# LKS_EVB_MVPOWPRE_V5_0.net
KiCad netlist of a schematic drawn in Altium Designer
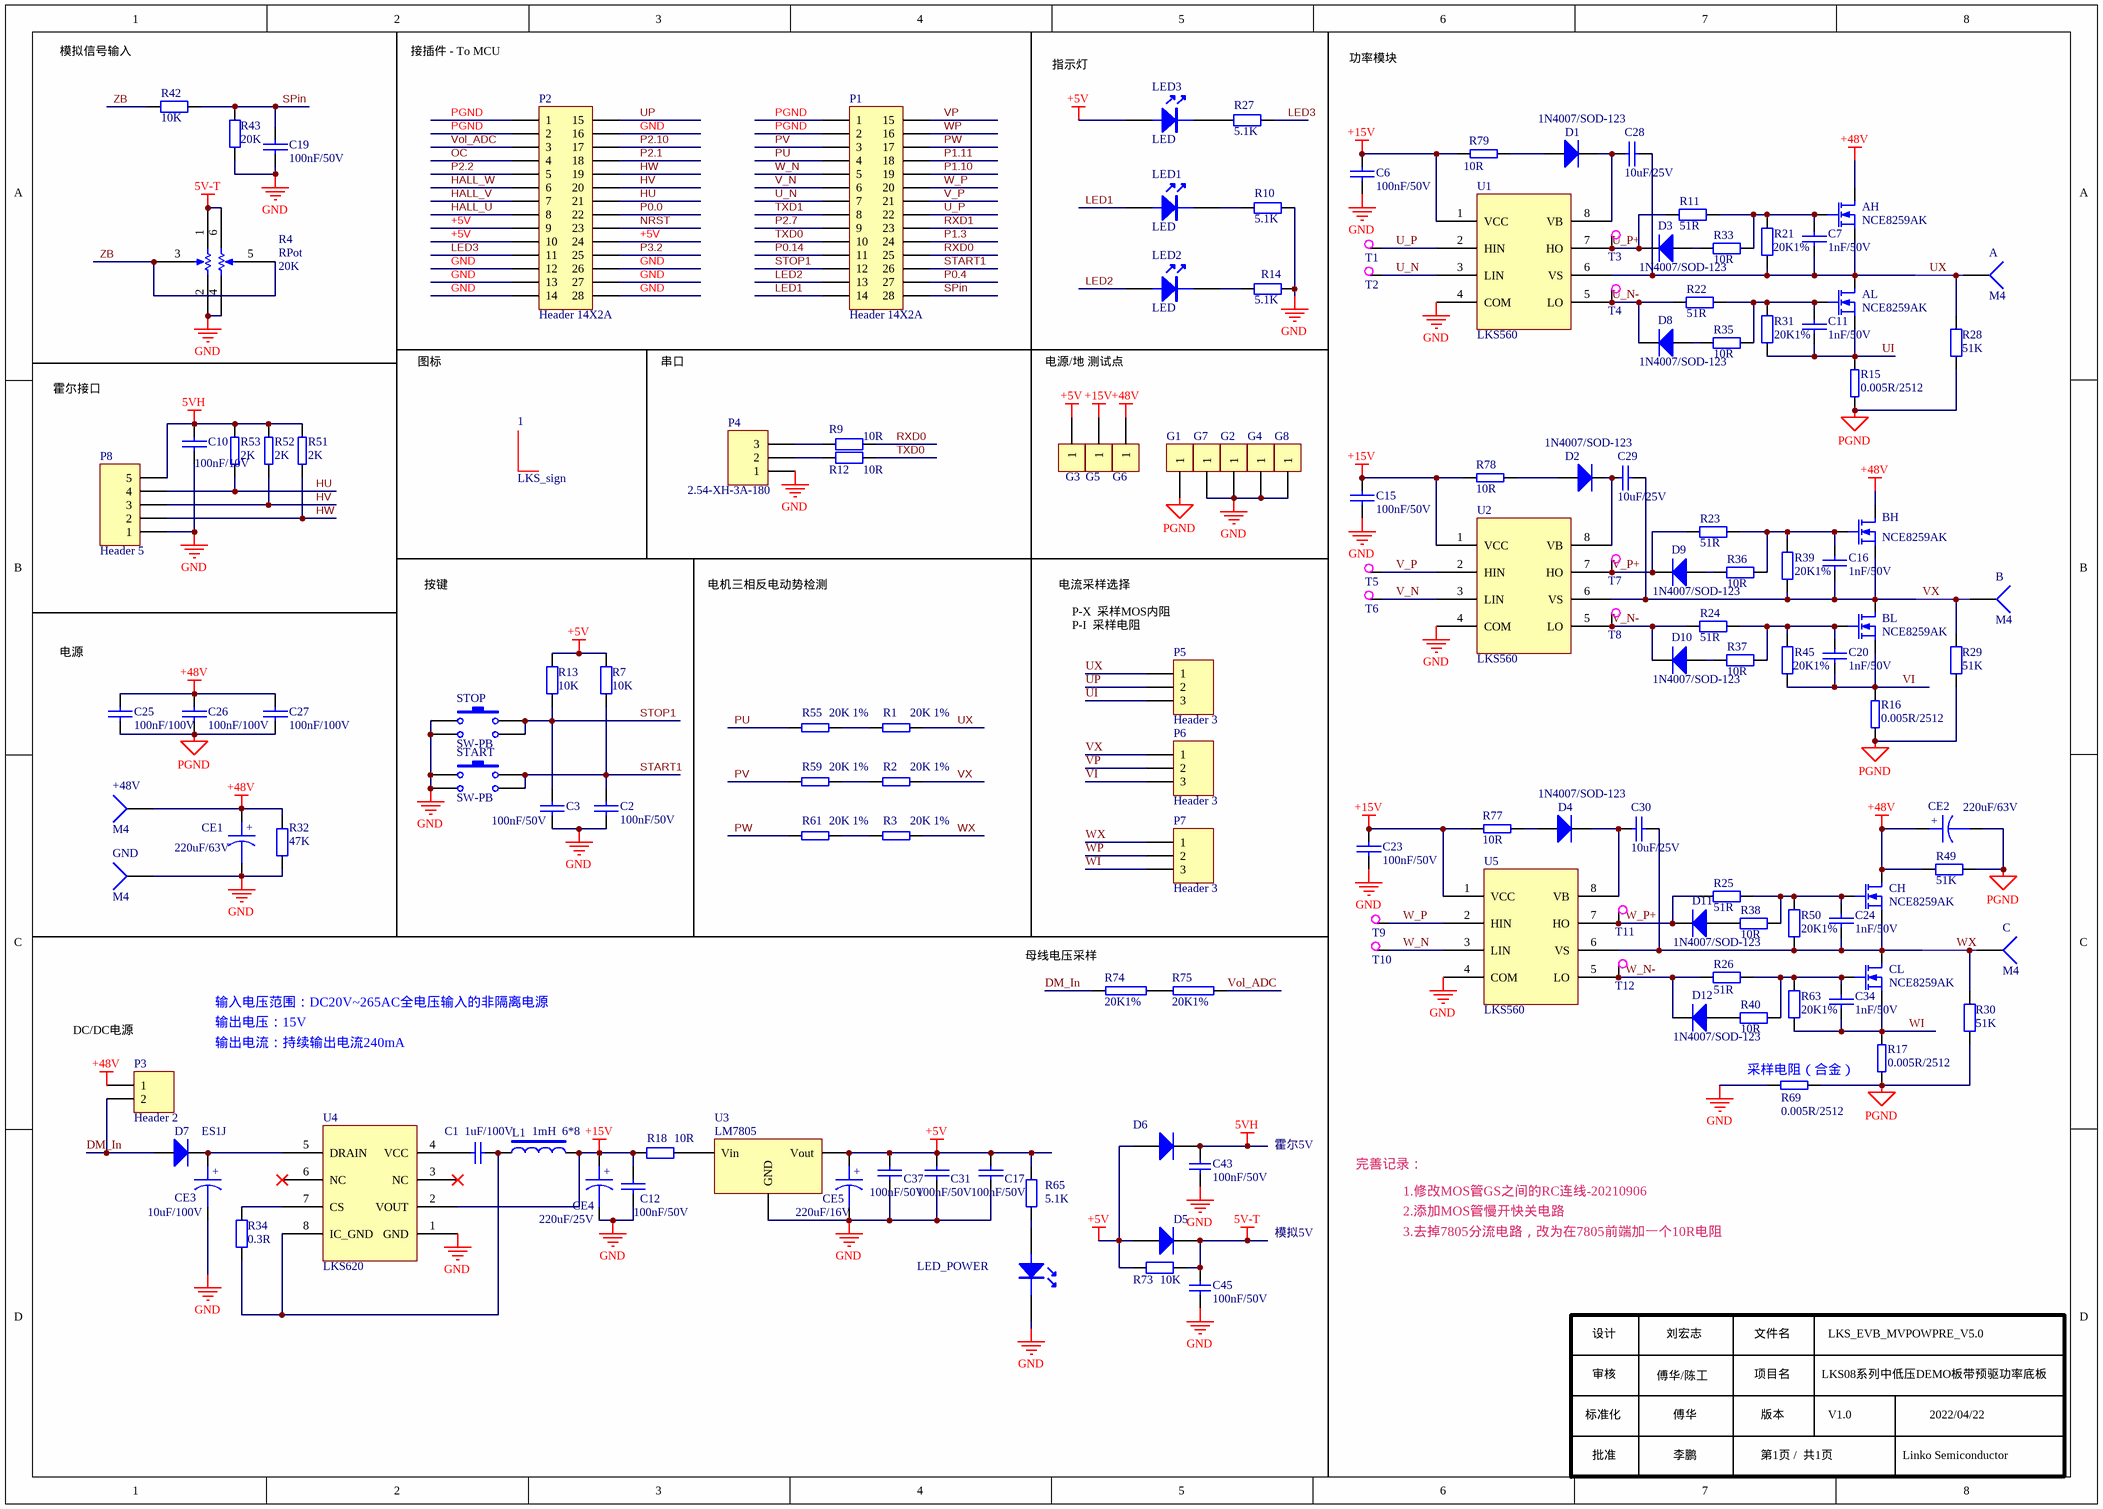
[diagram p0: LKS_EVB_MVPOWPRE_V5.0.SchDoc]

(export (version "E")
  (design (tool "Eeschema 10.0.6"))
  (components
    (comp (ref "+48V")
      (value "M4")
      (footprint "M4_CONECTOR")
      (description "Socket")
      (fields (field (name "PUBLISHER") "Altium Limited"))
      (libsource (lib "Miscellaneous Connectors") (part "Socket"))
    )
    (comp (ref "1")
      (value "LKS_sign")
      (footprint "LKS_LOGO2")
      (libsource (lib "linko sch library") (part "LKS_sign"))
    )
    (comp (ref "A")
      (value "M4")
      (footprint "M4_Conector")
      (description "Socket")
      (fields (field (name "PUBLISHER") "Altium Limited"))
      (libsource (lib "*") (part "Socket"))
    )
    (comp (ref "AH")
      (value "NCE8259AK")
      (footprint "TO-252")
      (libsource (lib "POWER-conponent") (part "MOS"))
    )
    (comp (ref "AL")
      (value "NCE8259AK")
      (footprint "TO-252")
      (libsource (lib "POWER-conponent") (part "MOS"))
    )
    (comp (ref "B")
      (value "M4")
      (footprint "M4_Conector")
      (description "Socket")
      (fields (field (name "PUBLISHER") "Altium Limited"))
      (libsource (lib "*") (part "Socket"))
    )
    (comp (ref "BH")
      (value "NCE8259AK")
      (footprint "TO-252")
      (libsource (lib "POWER-conponent") (part "MOS"))
    )
    (comp (ref "BL")
      (value "NCE8259AK")
      (footprint "TO-252")
      (libsource (lib "POWER-conponent") (part "MOS"))
    )
    (comp (ref "C")
      (value "M4")
      (footprint "M4_Conector")
      (description "Socket")
      (fields (field (name "PUBLISHER") "Altium Limited"))
      (libsource (lib "*") (part "Socket"))
    )
    (comp (ref "C1")
      (value "1uF/100V")
      (footprint "1206")
      (description "Capacitor")
      (fields (field (name "PUBLISHER") "Altium Limited"))
      (libsource (lib "Miscellaneous Devices") (part "Cap"))
    )
    (comp (ref "C2")
      (value "100nF/50V")
      (footprint "0603C")
      (description "Capacitor")
      (libsource (lib "GJ-BC-IC") (part "CAP"))
    )
    (comp (ref "C3")
      (value "100nF/50V")
      (footprint "0603C")
      (description "Capacitor")
      (libsource (lib "GJ-BC-IC") (part "CAP"))
    )
    (comp (ref "C6")
      (value "100nF/50V")
      (footprint "0603C")
      (description "Capacitor")
      (libsource (lib "*") (part "C"))
    )
    (comp (ref "C7")
      (value "1nF/50V")
      (footprint "0603C")
      (description "Capacitor")
      (libsource (lib "") (part "CAP_1"))
    )
    (comp (ref "C10")
      (value "100nF/10V")
      (footprint "0603C")
      (description "Capacitor")
      (libsource (lib "GJ-BC-IC") (part "CAP"))
    )
    (comp (ref "C11")
      (value "1nF/50V")
      (footprint "0603C")
      (description "Capacitor")
      (libsource (lib "") (part "CAP_1"))
    )
    (comp (ref "C12")
      (value "100nF/50V")
      (footprint "0603C")
      (description "Capacitor")
      (libsource (lib "*") (part "CAP"))
    )
    (comp (ref "C15")
      (value "100nF/50V")
      (footprint "0603C")
      (description "Capacitor")
      (libsource (lib "*") (part "C"))
    )
    (comp (ref "C16")
      (value "1nF/50V")
      (footprint "0603C")
      (description "Capacitor")
      (libsource (lib "") (part "CAP_1"))
    )
    (comp (ref "C17")
      (value "100nF/50V")
      (footprint "0603C")
      (description "Capacitor")
      (libsource (lib "*") (part "C"))
    )
    (comp (ref "C19")
      (value "100nF/50V")
      (footprint "0603C")
      (description "Capacitor")
      (libsource (lib "*") (part "C"))
    )
    (comp (ref "C20")
      (value "1nF/50V")
      (footprint "0603C")
      (description "Capacitor")
      (libsource (lib "") (part "CAP_1"))
    )
    (comp (ref "C23")
      (value "100nF/50V")
      (footprint "0603C")
      (description "Capacitor")
      (libsource (lib "*") (part "C"))
    )
    (comp (ref "C24")
      (value "1nF/50V")
      (footprint "0603C")
      (description "Capacitor")
      (libsource (lib "") (part "CAP_1"))
    )
    (comp (ref "C25")
      (value "100nF/100V")
      (footprint "0805C")
      (description "Capacitor")
      (libsource (lib "*") (part "CAP"))
    )
    (comp (ref "C26")
      (value "100nF/100V")
      (footprint "0805C")
      (description "Capacitor")
      (libsource (lib "*") (part "CAP"))
    )
    (comp (ref "C27")
      (value "100nF/100V")
      (footprint "0805C")
      (description "Capacitor")
      (libsource (lib "*") (part "CAP"))
    )
    (comp (ref "C28")
      (value "10uF/25V")
      (footprint "1206C")
      (description "Capacitor --贴片电容")
      (libsource (lib "LINKO_V1.0") (part "Capacitor"))
    )
    (comp (ref "C29")
      (value "10uF/25V")
      (footprint "1206C")
      (description "Capacitor --贴片电容")
      (libsource (lib "LINKO_V1.0") (part "Capacitor"))
    )
    (comp (ref "C30")
      (value "10uF/25V")
      (footprint "1206C")
      (description "Capacitor --贴片电容")
      (libsource (lib "LINKO_V1.0") (part "Capacitor"))
    )
    (comp (ref "C31")
      (value "100nF/50V")
      (footprint "0603C")
      (description "Capacitor")
      (libsource (lib "*") (part "C"))
    )
    (comp (ref "C34")
      (value "1nF/50V")
      (footprint "0603C")
      (description "Capacitor")
      (libsource (lib "") (part "CAP_1"))
    )
    (comp (ref "C37")
      (value "100nF/50V")
      (footprint "0603C")
      (description "Capacitor")
      (libsource (lib "*") (part "C"))
    )
    (comp (ref "C43")
      (value "100nF/50V")
      (footprint "0603C")
      (description "Capacitor")
      (fields (field (name "PUBLISHER") "Altium Limited"))
      (libsource (lib "Miscellaneous Devices") (part "Cap"))
    )
    (comp (ref "C45")
      (value "100nF/50V")
      (footprint "0603C")
      (description "Capacitor")
      (fields (field (name "PUBLISHER") "Altium Limited"))
      (libsource (lib "Miscellaneous Devices") (part "Cap"))
    )
    (comp (ref "CE1")
      (value "220uF/63V")
      (footprint "220UF/63V 12.5*12.5")
      (description "Capacitor---电解电容")
      (libsource (lib "LINKO_V1.0") (part "Capacitor Pol"))
    )
    (comp (ref "CE2")
      (value "220uF/63V")
      (footprint "220UF/63V 12.5*12.5")
      (description "Capacitor---电解电容")
      (libsource (lib "LINKO_V1.0") (part "Capacitor Pol"))
    )
    (comp (ref "CE3")
      (value "10uF/100V")
      (footprint "220UF/25V 8*10")
      (description "Capacitor---电解电容")
      (libsource (lib "LINKO_V1.0") (part "Capacitor Pol"))
    )
    (comp (ref "CE4")
      (value "220uF/25V")
      (footprint "220UF/25V 8*10")
      (description "Capacitor---电解电容")
      (libsource (lib "LINKO_V1.0") (part "Capacitor Pol"))
    )
    (comp (ref "CE5")
      (value "220uF/16V")
      (footprint "220UF/25V 8*10")
      (description "Capacitor---电解电容")
      (libsource (lib "LINKO_V1.0") (part "Capacitor Pol"))
    )
    (comp (ref "CH")
      (value "NCE8259AK")
      (footprint "TO-252")
      (libsource (lib "POWER-conponent") (part "MOS"))
    )
    (comp (ref "CL")
      (value "NCE8259AK")
      (footprint "TO-252")
      (libsource (lib "POWER-conponent") (part "MOS"))
    )
    (comp (ref "D1")
      (value "1N4007/SOD-123")
      (footprint "SOD123")
      (description "Default Diode")
      (fields (field (name "PUBLISHER") "Altium Limited"))
      (libsource (lib "*") (part "Diode"))
    )
    (comp (ref "D2")
      (value "1N4007/SOD-123")
      (footprint "SOD123")
      (description "Default Diode")
      (fields (field (name "PUBLISHER") "Altium Limited"))
      (libsource (lib "*") (part "Diode"))
    )
    (comp (ref "D3")
      (value "1N4007/SOD-123")
      (footprint "SOD123")
      (description "Default Diode")
      (fields (field (name "PUBLISHER") "Altium Limited"))
      (libsource (lib "*") (part "Diode"))
    )
    (comp (ref "D4")
      (value "1N4007/SOD-123")
      (footprint "SOD123")
      (description "Default Diode")
      (fields (field (name "PUBLISHER") "Altium Limited"))
      (libsource (lib "*") (part "Diode"))
    )
    (comp (ref "D5")
      (value "1N4007")
      (footprint "D1206")
      (description "1 Amp General Purpose Rectifier")
      (fields (field (name "PUBLISHER") "Altium Limited"))
      (libsource (lib "Miscellaneous Devices") (part "Diode 1N4007"))
    )
    (comp (ref "D6")
      (value "1N4007")
      (footprint "D1206")
      (description "1 Amp General Purpose Rectifier")
      (fields (field (name "PUBLISHER") "Altium Limited"))
      (libsource (lib "Miscellaneous Devices") (part "Diode 1N4007"))
    )
    (comp (ref "D7")
      (value "ES1J")
      (footprint "DO-214AC")
      (description "Default Diode")
      (fields (field (name "PUBLISHER") "Altium Limited"))
      (libsource (lib "*") (part "Diode"))
    )
    (comp (ref "D8")
      (value "1N4007/SOD-123")
      (footprint "SOD123")
      (description "Default Diode")
      (fields (field (name "PUBLISHER") "Altium Limited"))
      (libsource (lib "*") (part "Diode"))
    )
    (comp (ref "D9")
      (value "1N4007/SOD-123")
      (footprint "SOD123")
      (description "Default Diode")
      (fields (field (name "PUBLISHER") "Altium Limited"))
      (libsource (lib "*") (part "Diode"))
    )
    (comp (ref "D10")
      (value "1N4007/SOD-123")
      (footprint "SOD123")
      (description "Default Diode")
      (fields (field (name "PUBLISHER") "Altium Limited"))
      (libsource (lib "*") (part "Diode"))
    )
    (comp (ref "D11")
      (value "1N4007/SOD-123")
      (footprint "SOD123")
      (description "Default Diode")
      (fields (field (name "PUBLISHER") "Altium Limited"))
      (libsource (lib "*") (part "Diode"))
    )
    (comp (ref "D12")
      (value "1N4007/SOD-123")
      (footprint "SOD123")
      (description "Default Diode")
      (fields (field (name "PUBLISHER") "Altium Limited"))
      (libsource (lib "*") (part "Diode"))
    )
    (comp (ref "G1")
      (value "PAD1.2")
      (footprint "PAD1.2")
      (description "Connector")
      (libsource (lib "*") (part "CON1"))
    )
    (comp (ref "G2")
      (value "PAD1.2")
      (footprint "PAD1.2")
      (description "Connector")
      (libsource (lib "*") (part "CON1"))
    )
    (comp (ref "G3")
      (value "PAD1.2")
      (footprint "PAD1.2")
      (description "Connector")
      (libsource (lib "") (part "CON1_1"))
    )
    (comp (ref "G4")
      (value "PAD1.2")
      (footprint "PAD1.2")
      (description "Connector")
      (libsource (lib "*") (part "CON1"))
    )
    (comp (ref "G5")
      (value "PAD1.2")
      (footprint "PAD1.2")
      (description "Connector")
      (libsource (lib "") (part "CON1_1"))
    )
    (comp (ref "G6")
      (value "PAD1.2")
      (footprint "PAD1.2")
      (description "Connector")
      (libsource (lib "") (part "CON1_1"))
    )
    (comp (ref "G7")
      (value "PAD1.2")
      (footprint "PAD1.2")
      (description "Connector")
      (libsource (lib "*") (part "CON1"))
    )
    (comp (ref "G8")
      (value "PAD1.2")
      (footprint "PAD1.2")
      (description "Connector")
      (libsource (lib "*") (part "CON1"))
    )
    (comp (ref "GND")
      (value "M4")
      (footprint "M4_CONECTOR")
      (description "Socket")
      (fields (field (name "PUBLISHER") "Altium Limited"))
      (libsource (lib "Miscellaneous Connectors") (part "Socket"))
    )
    (comp (ref "L1") (value "1mH  6*8") (footprint "L_DIP_6*8MM") (libsource (lib "*") (part "L")))
    (comp (ref "LED1") (value "LED") (footprint "SOD323") (libsource (lib "GJ-BC-IC") (part "LED")))
    (comp (ref "LED2") (value "LED") (footprint "SOD323") (libsource (lib "GJ-BC-IC") (part "LED")))
    (comp (ref "LED3") (value "LED") (footprint "SOD323") (libsource (lib "GJ-BC-IC") (part "LED")))
    (comp (ref "LED_POWER") (value "LED_R") (footprint "SOD323") (libsource (lib "*") (part "LED")))
    (comp (ref "P1")
      (value "Header 14X2A")
      (footprint "HDR2X14_CEN")
      (description "Header, 14-Pin, Dual row")
      (fields (field (name "PUBLISHER") "Altium Limited"))
      (libsource (lib "Miscellaneous Connectors") (part "Header 14X2A"))
    )
    (comp (ref "P2")
      (value "Header 14X2A")
      (footprint "HDR2X14_CEN")
      (description "Header, 14-Pin, Dual row")
      (fields (field (name "PUBLISHER") "Altium Limited"))
      (libsource (lib "Miscellaneous Connectors") (part "Header 14X2A"))
    )
    (comp (ref "P3")
      (value "Header 2")
      (footprint "HDR1X2")
      (description "Header, 2-Pin")
      (fields (field (name "PUBLISHER") "Altium Limited"))
      (libsource (lib "Miscellaneous Connectors") (part "Header 2"))
    )
    (comp (ref "P4")
      (value "2.54-XH-3A-180")
      (footprint "2.54-XH-3A-180")
      (description "Header, 3-Pin")
      (fields (field (name "PUBLISHER") "Altium Limited"))
      (libsource (lib "Miscellaneous Connectors") (part "Header 3"))
    )
    (comp (ref "P5")
      (value "Header 3")
      (footprint "HDR1X3")
      (description "Header, 3-Pin")
      (fields (field (name "PUBLISHER") "Altium Limited"))
      (libsource (lib "") (part "Header 3_1"))
    )
    (comp (ref "P6")
      (value "Header 3")
      (footprint "HDR1X3")
      (description "Header, 3-Pin")
      (fields (field (name "PUBLISHER") "Altium Limited"))
      (libsource (lib "") (part "Header 3_1"))
    )
    (comp (ref "P7")
      (value "Header 3")
      (footprint "HDR1X3")
      (description "Header, 3-Pin")
      (fields (field (name "PUBLISHER") "Altium Limited"))
      (libsource (lib "") (part "Header 3_1"))
    )
    (comp (ref "P8")
      (value "Header 5")
      (footprint "2.54-XH-5A-180")
      (description "Header, 5-Pin")
      (fields (field (name "PUBLISHER") "Altium Limited"))
      (libsource (lib "Miscellaneous Connectors") (part "Header 5"))
    )
    (comp (ref "R1") (value "20K 1%") (footprint "0805R") (libsource (lib "LINKO_V1.0") (part "RES/1")))
    (comp (ref "R2") (value "20K 1%") (footprint "0805R") (libsource (lib "HenterLi") (part "RES/1")))
    (comp (ref "R3") (value "20K 1%") (footprint "0805R") (libsource (lib "HenterLi") (part "RES/1")))
    (comp (ref "R4")
      (value "RPot")
      (footprint "RK097-W-1")
      (description "Potentiometer")
      (fields (field (name "ALTIUM_VALUE") "20K") (field (name "PUBLISHER") "Altium Limited"))
      (libsource (lib "LKS_DEMO_V5.0") (part "RPot"))
    )
    (comp (ref "R7")
      (value "10K")
      (footprint "0603R")
      (description "Resistor")
      (fields (field (name "PUBLISHER") "Altium Limited"))
      (libsource (lib "") (part "Res2_2"))
    )
    (comp (ref "R9")
      (value "10R")
      (footprint "0603R")
      (description "Resistor")
      (fields (field (name "PUBLISHER") "Altium Limited"))
      (libsource (lib "Miscellaneous Devices") (part "Res2"))
    )
    (comp (ref "R10")
      (value "5.1K")
      (footprint "0603R")
      (description "Resistor")
      (fields (field (name "PUBLISHER") "Altium Limited"))
      (libsource (lib "GJ-BC-IC") (part "Res2"))
    )
    (comp (ref "R11")
      (value "51R")
      (footprint "0805R")
      (description "Resistor")
      (fields (field (name "PUBLISHER") "Altium Limited"))
      (libsource (lib "") (part "Res_1"))
    )
    (comp (ref "R12")
      (value "10R")
      (footprint "0603R")
      (description "Resistor")
      (fields (field (name "PUBLISHER") "Altium Limited"))
      (libsource (lib "") (part "Res2_1"))
    )
    (comp (ref "R13")
      (value "10K")
      (footprint "0603R")
      (description "Resistor")
      (fields (field (name "PUBLISHER") "Altium Limited"))
      (libsource (lib "") (part "Res2_1"))
    )
    (comp (ref "R14")
      (value "5.1K")
      (footprint "0603R")
      (description "Resistor")
      (fields (field (name "PUBLISHER") "Altium Limited"))
      (libsource (lib "GJ-BC-IC") (part "Res2"))
    )
    (comp (ref "R15") (value "0.005R/2512") (footprint "2512") (libsource (lib "*") (part "RES2短")))
    (comp (ref "R16") (value "0.005R/2512") (footprint "2512") (libsource (lib "*") (part "RES2短")))
    (comp (ref "R17") (value "0.005R/2512") (footprint "2512") (libsource (lib "*") (part "RES2短")))
    (comp (ref "R18")
      (value "10R")
      (footprint "1206R")
      (description "Resistor")
      (fields (field (name "PUBLISHER") "Altium Limited"))
      (libsource (lib "") (part "Res_1"))
    )
    (comp (ref "R21")
      (value "20K1%")
      (footprint "0603R")
      (description "Resistor")
      (fields (field (name "PUBLISHER") "Altium Limited"))
      (libsource (lib "LINKO_V1.0") (part "Res"))
    )
    (comp (ref "R22")
      (value "51R")
      (footprint "0805R")
      (description "Resistor")
      (fields (field (name "PUBLISHER") "Altium Limited"))
      (libsource (lib "") (part "Res_2"))
    )
    (comp (ref "R23")
      (value "51R")
      (footprint "0805R")
      (description "Resistor")
      (fields (field (name "PUBLISHER") "Altium Limited"))
      (libsource (lib "") (part "Res_1"))
    )
    (comp (ref "R24")
      (value "51R")
      (footprint "0805R")
      (description "Resistor")
      (fields (field (name "PUBLISHER") "Altium Limited"))
      (libsource (lib "") (part "Res_2"))
    )
    (comp (ref "R25")
      (value "51R")
      (footprint "0805R")
      (description "Resistor")
      (fields (field (name "PUBLISHER") "Altium Limited"))
      (libsource (lib "") (part "Res_1"))
    )
    (comp (ref "R26")
      (value "51R")
      (footprint "0805R")
      (description "Resistor")
      (fields (field (name "PUBLISHER") "Altium Limited"))
      (libsource (lib "") (part "Res_2"))
    )
    (comp (ref "R27")
      (value "5.1K")
      (footprint "0603R")
      (description "Resistor")
      (fields (field (name "PUBLISHER") "Altium Limited"))
      (libsource (lib "GJ-BC-IC") (part "Res2"))
    )
    (comp (ref "R28")
      (value "51K")
      (footprint "0805R")
      (description "Resistor")
      (fields (field (name "PUBLISHER") "Altium Limited"))
      (libsource (lib "LINKO_V1.0") (part "1Res"))
    )
    (comp (ref "R29")
      (value "51K")
      (footprint "0805R")
      (description "Resistor")
      (fields (field (name "PUBLISHER") "Altium Limited"))
      (libsource (lib "LINKO_V1.0") (part "1Res"))
    )
    (comp (ref "R30")
      (value "51K")
      (footprint "0805R")
      (description "Resistor")
      (fields (field (name "PUBLISHER") "Altium Limited"))
      (libsource (lib "LINKO_V1.0") (part "1Res"))
    )
    (comp (ref "R31")
      (value "20K1%")
      (footprint "0603R")
      (description "Resistor")
      (fields (field (name "PUBLISHER") "Altium Limited"))
      (libsource (lib "LINKO_V1.0") (part "Res"))
    )
    (comp (ref "R32")
      (value "47K")
      (footprint "1206R")
      (description "Resistor")
      (fields (field (name "PUBLISHER") "Altium Limited"))
      (libsource (lib "") (part "Res_3"))
    )
    (comp (ref "R33")
      (value "10R")
      (footprint "0805R")
      (description "Resistor")
      (fields (field (name "PUBLISHER") "Altium Limited"))
      (libsource (lib "") (part "Res_1"))
    )
    (comp (ref "R34")
      (value "0.3R")
      (footprint "1206")
      (description "Resistor")
      (fields (field (name "PUBLISHER") "Altium Limited"))
      (libsource (lib "Miscellaneous Devices") (part "Res2"))
    )
    (comp (ref "R35")
      (value "10R")
      (footprint "0805R")
      (description "Resistor")
      (fields (field (name "PUBLISHER") "Altium Limited"))
      (libsource (lib "") (part "1Res_1"))
    )
    (comp (ref "R36")
      (value "10R")
      (footprint "0805R")
      (description "Resistor")
      (fields (field (name "PUBLISHER") "Altium Limited"))
      (libsource (lib "") (part "1Res_1"))
    )
    (comp (ref "R37")
      (value "10R")
      (footprint "0805R")
      (description "Resistor")
      (fields (field (name "PUBLISHER") "Altium Limited"))
      (libsource (lib "") (part "1Res_1"))
    )
    (comp (ref "R38")
      (value "10R")
      (footprint "0805R")
      (description "Resistor")
      (fields (field (name "PUBLISHER") "Altium Limited"))
      (libsource (lib "") (part "1Res_1"))
    )
    (comp (ref "R39")
      (value "20K1%")
      (footprint "0603R")
      (description "Resistor")
      (fields (field (name "PUBLISHER") "Altium Limited"))
      (libsource (lib "LINKO_V1.0") (part "Res"))
    )
    (comp (ref "R40")
      (value "10R")
      (footprint "0805R")
      (description "Resistor")
      (fields (field (name "PUBLISHER") "Altium Limited"))
      (libsource (lib "") (part "1Res_1"))
    )
    (comp (ref "R42")
      (value "10K")
      (footprint "0603R")
      (description "Resistor")
      (fields (field (name "PUBLISHER") "Altium Limited"))
      (libsource (lib "") (part "Res_1"))
    )
    (comp (ref "R43")
      (value "20K")
      (footprint "0603R")
      (description "Resistor")
      (fields (field (name "PUBLISHER") "Altium Limited"))
      (libsource (lib "LINKO_V1.0") (part "Res"))
    )
    (comp (ref "R45")
      (value "20K1%")
      (footprint "0603R")
      (description "Resistor")
      (fields (field (name "PUBLISHER") "Altium Limited"))
      (libsource (lib "LINKO_V1.0") (part "Res"))
    )
    (comp (ref "R49")
      (value "51K")
      (footprint "0805R")
      (description "Resistor")
      (fields (field (name "PUBLISHER") "Altium Limited"))
      (libsource (lib "") (part "1Res_1"))
    )
    (comp (ref "R50")
      (value "20K1%")
      (footprint "0603R")
      (description "Resistor")
      (fields (field (name "PUBLISHER") "Altium Limited"))
      (libsource (lib "LINKO_V1.0") (part "Res"))
    )
    (comp (ref "R51") (value "2K") (footprint "0805R") (libsource (lib "") (part "RES/1_1")))
    (comp (ref "R52") (value "2K") (footprint "0805R") (libsource (lib "") (part "RES/1_1")))
    (comp (ref "R53") (value "2K") (footprint "0805R") (libsource (lib "") (part "RES/1_1")))
    (comp (ref "R55") (value "20K 1%") (footprint "0805R") (libsource (lib "HenterLi") (part "RES/1")))
    (comp (ref "R59") (value "20K 1%") (footprint "0805R") (libsource (lib "HenterLi") (part "RES/1")))
    (comp (ref "R61") (value "20K 1%") (footprint "0805R") (libsource (lib "HenterLi") (part "RES/1")))
    (comp (ref "R63")
      (value "20K1%")
      (footprint "0603R")
      (description "Resistor")
      (fields (field (name "PUBLISHER") "Altium Limited"))
      (libsource (lib "LINKO_V1.0") (part "Res"))
    )
    (comp (ref "R65")
      (value "5.1K")
      (footprint "0603R")
      (description "Resistor")
      (fields (field (name "PUBLISHER") "Altium Limited"))
      (libsource (lib "LINKO_V1.0") (part "Res2"))
    )
    (comp (ref "R69") (value "0.005R/2512") (footprint "2512") (libsource (lib "*") (part "RES2短")))
    (comp (ref "R73")
      (value "10K")
      (footprint "0603R")
      (description "Resistor")
      (fields (field (name "PUBLISHER") "Altium Limited"))
      (libsource (lib "") (part "Res2_2"))
    )
    (comp (ref "R74") (value "20K1%") (footprint "0603R") (libsource (lib "*") (part "R")))
    (comp (ref "R75") (value "20K1%") (footprint "0603R") (libsource (lib "*") (part "R")))
    (comp (ref "R77") (value "10R") (footprint "0805r") (libsource (lib "*") (part "RES2短")))
    (comp (ref "R78") (value "10R") (footprint "0805r") (libsource (lib "*") (part "RES2短")))
    (comp (ref "R79") (value "10R") (footprint "0805r") (libsource (lib "*") (part "RES2短")))
    (comp (ref "START")
      (value "SW-PB")
      (footprint "SW-PB  12*12")
      (description "Switch")
      (fields (field (name "PUBLISHER") "Altium Limited"))
      (libsource (lib "LKS_DEMO_081_V4.0") (part "SW-PB"))
    )
    (comp (ref "STOP")
      (value "SW-PB")
      (footprint "SW-PB  12*12")
      (description "Switch")
      (fields (field (name "PUBLISHER") "Altium Limited"))
      (libsource (lib "LKS_DEMO_081_V4.0") (part "SW-PB"))
    )
    (comp (ref "T1") (value "TestP") (footprint "TP-80") (libsource (lib "LINKO_V1.0") (part "TestP")))
    (comp (ref "T2") (value "TestP") (footprint "TP-80") (libsource (lib "LINKO_V1.0") (part "TestP")))
    (comp (ref "T3") (value "TestP") (footprint "TP-80") (libsource (lib "LINKO_V1.0") (part "TestP")))
    (comp (ref "T4") (value "TestP") (footprint "TP-80") (libsource (lib "LINKO_V1.0") (part "TestP")))
    (comp (ref "T5") (value "TestP") (footprint "TP-80") (libsource (lib "LINKO_V1.0") (part "TestP")))
    (comp (ref "T6") (value "TestP") (footprint "TP-80") (libsource (lib "LINKO_V1.0") (part "TestP")))
    (comp (ref "T7") (value "TestP") (footprint "TP-80") (libsource (lib "LINKO_V1.0") (part "TestP")))
    (comp (ref "T8") (value "TestP") (footprint "TP-80") (libsource (lib "LINKO_V1.0") (part "TestP")))
    (comp (ref "T9") (value "TestP") (footprint "TP-80") (libsource (lib "LINKO_V1.0") (part "TestP")))
    (comp (ref "T10") (value "TestP") (footprint "TP-80") (libsource (lib "LINKO_V1.0") (part "TestP")))
    (comp (ref "T11") (value "TestP") (footprint "TP-80") (libsource (lib "LINKO_V1.0") (part "TestP")))
    (comp (ref "T12") (value "TestP") (footprint "TP-80") (libsource (lib "LINKO_V1.0") (part "TestP")))
    (comp (ref "U1") (value "LKS560") (footprint "SO-8") (libsource (lib "MY_SCH") (part "IRS2003S")))
    (comp (ref "U2") (value "LKS560") (footprint "SO-8") (libsource (lib "MY_SCH") (part "IRS2003S")))
    (comp (ref "U3")
      (value "LM7805")
      (footprint "linko pcb library:SOT-89")
      (libsource (lib "*") (part "VOL-78"))
    )
    (comp (ref "U4") (value "LKS620") (footprint "SO-8") (libsource (lib "081-620") (part "LKS620")))
    (comp (ref "U5") (value "LKS560") (footprint "SO-8") (libsource (lib "MY_SCH") (part "IRS2003S")))
  )
  (nets
    (net (code "1") (name "+5V") (class "Default")
      (node (ref "C17") (pin "2") (pinfunction "2_2") (pintype "passive"))
      (node (ref "C31") (pin "2") (pinfunction "2_2") (pintype "passive"))
      (node (ref "C37") (pin "2") (pinfunction "2_2") (pintype "passive"))
      (node (ref "CE5") (pin "1") (pinfunction "1_1") (pintype "passive"))
      (node (ref "D5") (pin "1") (pinfunction "A_1") (pintype "passive"))
      (node (ref "D6") (pin "1") (pinfunction "A_1") (pintype "passive"))
      (node (ref "G3") (pin "1") (pinfunction "1_1") (pintype "passive"))
      (node (ref "LED3") (pin "1") (pinfunction "A_1") (pintype "passive"))
      (node (ref "P2") (pin "10") (pinfunction "10_10") (pintype "passive"))
      (node (ref "P2") (pin "24") (pinfunction "24_24") (pintype "passive"))
      (node (ref "P2") (pin "9") (pinfunction "9_9") (pintype "passive"))
      (node (ref "R13") (pin "2") (pinfunction "2_2") (pintype "passive"))
      (node (ref "R65") (pin "1") (pinfunction "1_1") (pintype "passive"))
      (node (ref "R7") (pin "1") (pinfunction "1_1") (pintype "passive"))
      (node (ref "R73") (pin "1") (pinfunction "1_1") (pintype "passive"))
      (node (ref "U3") (pin "1") (pinfunction "Vout_1") (pintype "passive"))
    )
    (net (code "2") (name "+15V") (class "Default")
      (node (ref "C12") (pin "1") (pinfunction "1_1") (pintype "passive"))
      (node (ref "C15") (pin "2") (pinfunction "2_2") (pintype "passive"))
      (node (ref "C23") (pin "2") (pinfunction "2_2") (pintype "passive"))
      (node (ref "C6") (pin "2") (pinfunction "2_2") (pintype "passive"))
      (node (ref "CE4") (pin "1") (pinfunction "1_1") (pintype "passive"))
      (node (ref "G5") (pin "1") (pinfunction "1_1") (pintype "passive"))
      (node (ref "L1") (pin "1") (pinfunction "1_1") (pintype "passive"))
      (node (ref "R18") (pin "1") (pinfunction "1_1") (pintype "passive"))
      (node (ref "R77") (pin "1") (pinfunction "1_1") (pintype "passive"))
      (node (ref "R78") (pin "1") (pinfunction "1_1") (pintype "passive"))
      (node (ref "R79") (pin "1") (pinfunction "1_1") (pintype "passive"))
      (node (ref "U1") (pin "1") (pinfunction "VCC_1") (pintype "passive"))
      (node (ref "U2") (pin "1") (pinfunction "VCC_1") (pintype "passive"))
      (node (ref "U4") (pin "2") (pinfunction "VOUT_2") (pintype "passive"))
      (node (ref "U5") (pin "1") (pinfunction "VCC_1") (pintype "passive"))
    )
    (net (code "3") (name "+48V") (class "Default")
      (node (ref "+48V") (pin "1") (pinfunction "1_1") (pintype "passive"))
      (node (ref "AH") (pin "2") (pinfunction "D_2") (pintype "passive"))
      (node (ref "BH") (pin "2") (pinfunction "D_2") (pintype "passive"))
      (node (ref "C25") (pin "2") (pinfunction "2_2") (pintype "passive"))
      (node (ref "C26") (pin "2") (pinfunction "2_2") (pintype "passive"))
      (node (ref "C27") (pin "2") (pinfunction "2_2") (pintype "passive"))
      (node (ref "CE1") (pin "1") (pinfunction "1_1") (pintype "passive"))
      (node (ref "CE2") (pin "1") (pinfunction "1_1") (pintype "passive"))
      (node (ref "CH") (pin "2") (pinfunction "D_2") (pintype "passive"))
      (node (ref "G6") (pin "1") (pinfunction "1_1") (pintype "passive"))
      (node (ref "P3") (pin "1") (pinfunction "1_1") (pintype "passive"))
      (node (ref "R32") (pin "1") (pinfunction "1_1") (pintype "passive"))
      (node (ref "R49") (pin "1") (pinfunction "1_1") (pintype "passive"))
    )
    (net (code "4") (name "/DM_In") (class "Default")
      (node (ref "D7") (pin "1") (pinfunction "A_1") (pintype "passive"))
      (node (ref "P3") (pin "2") (pinfunction "2_2") (pintype "passive"))
      (node (ref "R74") (pin "1") (pinfunction "1_1") (pintype "passive"))
    )
    (net (code "5") (name "/HALL_U") (class "Default")
      (node (ref "P2") (pin "8") (pinfunction "8_8") (pintype "passive"))
    )
    (net (code "6") (name "/HALL_V") (class "Default")
      (node (ref "P2") (pin "7") (pinfunction "7_7") (pintype "passive"))
    )
    (net (code "7") (name "/HALL_W") (class "Default")
      (node (ref "P2") (pin "6") (pinfunction "6_6") (pintype "passive"))
    )
    (net (code "8") (name "/HU") (class "Default")
      (node (ref "P2") (pin "21") (pinfunction "21_21") (pintype "passive"))
      (node (ref "P8") (pin "4") (pinfunction "4_4") (pintype "passive"))
      (node (ref "R53") (pin "1") (pinfunction "1_1") (pintype "passive"))
    )
    (net (code "9") (name "/HV") (class "Default")
      (node (ref "P2") (pin "20") (pinfunction "20_20") (pintype "passive"))
      (node (ref "P8") (pin "3") (pinfunction "3_3") (pintype "passive"))
      (node (ref "R52") (pin "1") (pinfunction "1_1") (pintype "passive"))
    )
    (net (code "10") (name "/HW") (class "Default")
      (node (ref "P2") (pin "19") (pinfunction "19_19") (pintype "passive"))
      (node (ref "P8") (pin "2") (pinfunction "2_2") (pintype "passive"))
      (node (ref "R51") (pin "1") (pinfunction "1_1") (pintype "passive"))
    )
    (net (code "11") (name "/LED1") (class "Default")
      (node (ref "LED1") (pin "1") (pinfunction "A_1") (pintype "passive"))
      (node (ref "P1") (pin "14") (pinfunction "14_14") (pintype "passive"))
    )
    (net (code "12") (name "/LED2") (class "Default")
      (node (ref "LED2") (pin "1") (pinfunction "A_1") (pintype "passive"))
      (node (ref "P1") (pin "13") (pinfunction "13_13") (pintype "passive"))
    )
    (net (code "13") (name "/LED3") (class "Default")
      (node (ref "P2") (pin "11") (pinfunction "11_11") (pintype "passive"))
      (node (ref "R27") (pin "2") (pinfunction "2_2") (pintype "passive"))
    )
    (net (code "14") (name "/NRST") (class "Default")
      (node (ref "P2") (pin "23") (pinfunction "23_23") (pintype "passive"))
    )
    (net (code "15") (name "/OC") (class "Default")
      (node (ref "P2") (pin "4") (pinfunction "4_4") (pintype "passive"))
    )
    (net (code "16") (name "/P0.0") (class "Default")
      (node (ref "P2") (pin "22") (pinfunction "22_22") (pintype "passive"))
    )
    (net (code "17") (name "/P0.4") (class "Default")
      (node (ref "P1") (pin "27") (pinfunction "27_27") (pintype "passive"))
    )
    (net (code "18") (name "/P0.14") (class "Default")
      (node (ref "P1") (pin "11") (pinfunction "11_11") (pintype "passive"))
    )
    (net (code "19") (name "/P1.3") (class "Default")
      (node (ref "P1") (pin "24") (pinfunction "24_24") (pintype "passive"))
    )
    (net (code "20") (name "/P1.10") (class "Default")
      (node (ref "P1") (pin "19") (pinfunction "19_19") (pintype "passive"))
    )
    (net (code "21") (name "/P1.11") (class "Default")
      (node (ref "P1") (pin "18") (pinfunction "18_18") (pintype "passive"))
    )
    (net (code "22") (name "/P2.1") (class "Default")
      (node (ref "P2") (pin "18") (pinfunction "18_18") (pintype "passive"))
    )
    (net (code "23") (name "/P2.2") (class "Default")
      (node (ref "P2") (pin "5") (pinfunction "5_5") (pintype "passive"))
    )
    (net (code "24") (name "/P2.7") (class "Default")
      (node (ref "P1") (pin "9") (pinfunction "9_9") (pintype "passive"))
    )
    (net (code "25") (name "/P2.10") (class "Default")
      (node (ref "P2") (pin "17") (pinfunction "17_17") (pintype "passive"))
    )
    (net (code "26") (name "/P3.2") (class "Default")
      (node (ref "P2") (pin "25") (pinfunction "25_25") (pintype "passive"))
    )
    (net (code "27") (name "/PU") (class "Default")
      (node (ref "P1") (pin "4") (pinfunction "4_4") (pintype "passive"))
      (node (ref "R55") (pin "1") (pinfunction "1_1") (pintype "passive"))
    )
    (net (code "28") (name "/PV") (class "Default")
      (node (ref "P1") (pin "3") (pinfunction "3_3") (pintype "passive"))
      (node (ref "R59") (pin "1") (pinfunction "1_1") (pintype "passive"))
    )
    (net (code "29") (name "/PW") (class "Default")
      (node (ref "P1") (pin "17") (pinfunction "17_17") (pintype "passive"))
      (node (ref "R61") (pin "1") (pinfunction "1_1") (pintype "passive"))
    )
    (net (code "30") (name "/RXD0") (class "Default")
      (node (ref "P1") (pin "25") (pinfunction "25_25") (pintype "passive"))
      (node (ref "R9") (pin "1") (pinfunction "1_1") (pintype "passive"))
    )
    (net (code "31") (name "/RXD1") (class "Default")
      (node (ref "P1") (pin "23") (pinfunction "23_23") (pintype "passive"))
    )
    (net (code "32") (name "/SPin") (class "Default")
      (node (ref "C19") (pin "2") (pinfunction "2_2") (pintype "passive"))
      (node (ref "P1") (pin "28") (pinfunction "28_28") (pintype "passive"))
      (node (ref "R42") (pin "2") (pinfunction "2_2") (pintype "passive"))
      (node (ref "R43") (pin "2") (pinfunction "2_2") (pintype "passive"))
    )
    (net (code "33") (name "/START1") (class "Default")
      (node (ref "C2") (pin "2") (pinfunction "2_2") (pintype "passive"))
      (node (ref "P1") (pin "26") (pinfunction "26_26") (pintype "passive"))
      (node (ref "R7") (pin "2") (pinfunction "2_2") (pintype "passive"))
      (node (ref "START") (pin "2") (pinfunction "2_2") (pintype "passive"))
      (node (ref "START") (pin "4") (pinfunction "4_4") (pintype "passive"))
    )
    (net (code "34") (name "/STOP1") (class "Default")
      (node (ref "C3") (pin "1") (pinfunction "1_1") (pintype "passive"))
      (node (ref "P1") (pin "12") (pinfunction "12_12") (pintype "passive"))
      (node (ref "R13") (pin "1") (pinfunction "1_1") (pintype "passive"))
      (node (ref "STOP") (pin "2") (pinfunction "2_2") (pintype "passive"))
      (node (ref "STOP") (pin "4") (pinfunction "4_4") (pintype "passive"))
    )
    (net (code "35") (name "/TXD0") (class "Default")
      (node (ref "P1") (pin "10") (pinfunction "10_10") (pintype "passive"))
      (node (ref "R12") (pin "2") (pinfunction "2_2") (pintype "passive"))
    )
    (net (code "36") (name "/TXD1") (class "Default")
      (node (ref "P1") (pin "8") (pinfunction "8_8") (pintype "passive"))
    )
    (net (code "37") (name "/UI") (class "Default")
      (node (ref "AL") (pin "3") (pinfunction "S_3") (pintype "passive"))
      (node (ref "C11") (pin "2") (pinfunction "2_2") (pintype "passive"))
      (node (ref "P5") (pin "3") (pinfunction "3_3") (pintype "passive"))
      (node (ref "R15") (pin "1") (pinfunction "1_1") (pintype "passive"))
      (node (ref "R31") (pin "1") (pinfunction "1_1") (pintype "passive"))
    )
    (net (code "38") (name "/UP") (class "Default")
      (node (ref "P2") (pin "15") (pinfunction "15_15") (pintype "passive"))
      (node (ref "P5") (pin "2") (pinfunction "2_2") (pintype "passive"))
    )
    (net (code "39") (name "/UX") (class "Default")
      (node (ref "A") (pin "1") (pinfunction "1_1") (pintype "passive"))
      (node (ref "AH") (pin "3") (pinfunction "S_3") (pintype "passive"))
      (node (ref "AL") (pin "2") (pinfunction "D_2") (pintype "passive"))
      (node (ref "C28") (pin "2") (pinfunction "2_2") (pintype "passive"))
      (node (ref "C7") (pin "2") (pinfunction "2_2") (pintype "passive"))
      (node (ref "P5") (pin "1") (pinfunction "1_1") (pintype "passive"))
      (node (ref "R1") (pin "2") (pinfunction "2_2") (pintype "passive"))
      (node (ref "R21") (pin "1") (pinfunction "1_1") (pintype "passive"))
      (node (ref "R28") (pin "2") (pinfunction "2_2") (pintype "passive"))
      (node (ref "U1") (pin "6") (pinfunction "VS_6") (pintype "passive"))
    )
    (net (code "40") (name "/U_N") (class "Default")
      (node (ref "P1") (pin "7") (pinfunction "7_7") (pintype "passive"))
      (node (ref "T2") (pin "1") (pintype "passive"))
      (node (ref "U1") (pin "3") (pinfunction "LIN_3") (pintype "passive"))
    )
    (net (code "41") (name "/U_N-") (class "Default")
      (node (ref "D8") (pin "2") (pinfunction "K_2") (pintype "passive"))
      (node (ref "R22") (pin "2") (pinfunction "2_2") (pintype "passive"))
      (node (ref "T4") (pin "1") (pintype "passive"))
      (node (ref "U1") (pin "5") (pinfunction "LO_5") (pintype "passive"))
    )
    (net (code "42") (name "/U_P") (class "Default")
      (node (ref "P1") (pin "22") (pinfunction "22_22") (pintype "passive"))
      (node (ref "T1") (pin "1") (pintype "passive"))
      (node (ref "U1") (pin "2") (pinfunction "HIN_2") (pintype "passive"))
    )
    (net (code "43") (name "/U_P+") (class "Default")
      (node (ref "D3") (pin "2") (pinfunction "K_2") (pintype "passive"))
      (node (ref "R11") (pin "1") (pinfunction "1_1") (pintype "passive"))
      (node (ref "T3") (pin "1") (pintype "passive"))
      (node (ref "U1") (pin "7") (pinfunction "HO_7") (pintype "passive"))
    )
    (net (code "44") (name "/VI") (class "Default")
      (node (ref "BL") (pin "3") (pinfunction "S_3") (pintype "passive"))
      (node (ref "C20") (pin "2") (pinfunction "2_2") (pintype "passive"))
      (node (ref "P6") (pin "3") (pinfunction "3_3") (pintype "passive"))
      (node (ref "R16") (pin "2") (pinfunction "2_2") (pintype "passive"))
      (node (ref "R45") (pin "1") (pinfunction "1_1") (pintype "passive"))
    )
    (net (code "45") (name "/VP") (class "Default")
      (node (ref "P1") (pin "15") (pinfunction "15_15") (pintype "passive"))
      (node (ref "P6") (pin "2") (pinfunction "2_2") (pintype "passive"))
    )
    (net (code "46") (name "/VX") (class "Default")
      (node (ref "B") (pin "1") (pinfunction "1_1") (pintype "passive"))
      (node (ref "BH") (pin "3") (pinfunction "S_3") (pintype "passive"))
      (node (ref "BL") (pin "2") (pinfunction "D_2") (pintype "passive"))
      (node (ref "C16") (pin "2") (pinfunction "2_2") (pintype "passive"))
      (node (ref "C29") (pin "2") (pinfunction "2_2") (pintype "passive"))
      (node (ref "P6") (pin "1") (pinfunction "1_1") (pintype "passive"))
      (node (ref "R2") (pin "2") (pinfunction "2_2") (pintype "passive"))
      (node (ref "R29") (pin "2") (pinfunction "2_2") (pintype "passive"))
      (node (ref "R39") (pin "1") (pinfunction "1_1") (pintype "passive"))
      (node (ref "U2") (pin "6") (pinfunction "VS_6") (pintype "passive"))
    )
    (net (code "47") (name "/V_N") (class "Default")
      (node (ref "P1") (pin "6") (pinfunction "6_6") (pintype "passive"))
      (node (ref "T6") (pin "1") (pintype "passive"))
      (node (ref "U2") (pin "3") (pinfunction "LIN_3") (pintype "passive"))
    )
    (net (code "48") (name "/V_N-") (class "Default")
      (node (ref "D10") (pin "2") (pinfunction "K_2") (pintype "passive"))
      (node (ref "R24") (pin "2") (pinfunction "2_2") (pintype "passive"))
      (node (ref "T8") (pin "1") (pintype "passive"))
      (node (ref "U2") (pin "5") (pinfunction "LO_5") (pintype "passive"))
    )
    (net (code "49") (name "/V_P") (class "Default")
      (node (ref "P1") (pin "21") (pinfunction "21_21") (pintype "passive"))
      (node (ref "T5") (pin "1") (pintype "passive"))
      (node (ref "U2") (pin "2") (pinfunction "HIN_2") (pintype "passive"))
    )
    (net (code "50") (name "/V_P+") (class "Default")
      (node (ref "D9") (pin "2") (pinfunction "K_2") (pintype "passive"))
      (node (ref "R23") (pin "1") (pinfunction "1_1") (pintype "passive"))
      (node (ref "T7") (pin "1") (pintype "passive"))
      (node (ref "U2") (pin "7") (pinfunction "HO_7") (pintype "passive"))
    )
    (net (code "51") (name "/Vol_ADC") (class "Default")
      (node (ref "P2") (pin "3") (pinfunction "3_3") (pintype "passive"))
      (node (ref "R75") (pin "2") (pinfunction "2_2") (pintype "passive"))
    )
    (net (code "52") (name "/WI") (class "Default")
      (node (ref "C34") (pin "2") (pinfunction "2_2") (pintype "passive"))
      (node (ref "CL") (pin "3") (pinfunction "S_3") (pintype "passive"))
      (node (ref "P7") (pin "3") (pinfunction "3_3") (pintype "passive"))
      (node (ref "R17") (pin "1") (pinfunction "1_1") (pintype "passive"))
      (node (ref "R63") (pin "1") (pinfunction "1_1") (pintype "passive"))
    )
    (net (code "53") (name "/WP") (class "Default")
      (node (ref "P1") (pin "16") (pinfunction "16_16") (pintype "passive"))
      (node (ref "P7") (pin "2") (pinfunction "2_2") (pintype "passive"))
    )
    (net (code "54") (name "/WX") (class "Default")
      (node (ref "C") (pin "1") (pinfunction "1_1") (pintype "passive"))
      (node (ref "C24") (pin "2") (pinfunction "2_2") (pintype "passive"))
      (node (ref "C30") (pin "2") (pinfunction "2_2") (pintype "passive"))
      (node (ref "CH") (pin "3") (pinfunction "S_3") (pintype "passive"))
      (node (ref "CL") (pin "2") (pinfunction "D_2") (pintype "passive"))
      (node (ref "P7") (pin "1") (pinfunction "1_1") (pintype "passive"))
      (node (ref "R3") (pin "2") (pinfunction "2_2") (pintype "passive"))
      (node (ref "R30") (pin "2") (pinfunction "2_2") (pintype "passive"))
      (node (ref "R50") (pin "1") (pinfunction "1_1") (pintype "passive"))
      (node (ref "U5") (pin "6") (pinfunction "VS_6") (pintype "passive"))
    )
    (net (code "55") (name "/W_N") (class "Default")
      (node (ref "P1") (pin "5") (pinfunction "5_5") (pintype "passive"))
      (node (ref "T10") (pin "1") (pintype "passive"))
      (node (ref "U5") (pin "3") (pinfunction "LIN_3") (pintype "passive"))
    )
    (net (code "56") (name "/W_N-") (class "Default")
      (node (ref "D12") (pin "2") (pinfunction "K_2") (pintype "passive"))
      (node (ref "R26") (pin "2") (pinfunction "2_2") (pintype "passive"))
      (node (ref "T12") (pin "1") (pintype "passive"))
      (node (ref "U5") (pin "5") (pinfunction "LO_5") (pintype "passive"))
    )
    (net (code "57") (name "/W_P") (class "Default")
      (node (ref "P1") (pin "20") (pinfunction "20_20") (pintype "passive"))
      (node (ref "T9") (pin "1") (pintype "passive"))
      (node (ref "U5") (pin "2") (pinfunction "HIN_2") (pintype "passive"))
    )
    (net (code "58") (name "/W_P+") (class "Default")
      (node (ref "D11") (pin "2") (pinfunction "K_2") (pintype "passive"))
      (node (ref "R25") (pin "1") (pinfunction "1_1") (pintype "passive"))
      (node (ref "T11") (pin "1") (pintype "passive"))
      (node (ref "U5") (pin "7") (pinfunction "HO_7") (pintype "passive"))
    )
    (net (code "59") (name "/ZB") (class "Default")
      (node (ref "R4") (pin "3") (pinfunction "BOT_3") (pintype "passive"))
      (node (ref "R4") (pin "5") (pinfunction "TAP_5") (pintype "passive"))
      (node (ref "R42") (pin "1") (pinfunction "1_1") (pintype "passive"))
    )
    (net (code "62") (name "5V-T") (class "Default")
      (node (ref "C45") (pin "2") (pinfunction "2_2") (pintype "passive"))
      (node (ref "D5") (pin "2") (pinfunction "K_2") (pintype "passive"))
      (node (ref "R4") (pin "1") (pinfunction "TOP_1") (pintype "passive"))
      (node (ref "R4") (pin "6") (pinfunction "TOP_6") (pintype "passive"))
      (node (ref "R73") (pin "2") (pinfunction "2_2") (pintype "passive"))
    )
    (net (code "63") (name "5VH") (class "Default")
      (node (ref "C10") (pin "1") (pinfunction "1_1") (pintype "passive"))
      (node (ref "C43") (pin "2") (pinfunction "2_2") (pintype "passive"))
      (node (ref "D6") (pin "2") (pinfunction "K_2") (pintype "passive"))
      (node (ref "P8") (pin "5") (pinfunction "5_5") (pintype "passive"))
      (node (ref "R51") (pin "2") (pinfunction "2_2") (pintype "passive"))
      (node (ref "R52") (pin "2") (pinfunction "2_2") (pintype "passive"))
      (node (ref "R53") (pin "2") (pinfunction "2_2") (pintype "passive"))
    )
    (net (code "64") (name "GND") (class "Default")
      (node (ref "C10") (pin "2") (pinfunction "2_2") (pintype "passive"))
      (node (ref "C12") (pin "2") (pinfunction "2_2") (pintype "passive"))
      (node (ref "C15") (pin "1") (pinfunction "1_1") (pintype "passive"))
      (node (ref "C17") (pin "1") (pinfunction "1_1") (pintype "passive"))
      (node (ref "C19") (pin "1") (pinfunction "1_1") (pintype "passive"))
      (node (ref "C2") (pin "1") (pinfunction "1_1") (pintype "passive"))
      (node (ref "C23") (pin "1") (pinfunction "1_1") (pintype "passive"))
      (node (ref "C3") (pin "2") (pinfunction "2_2") (pintype "passive"))
      (node (ref "C31") (pin "1") (pinfunction "1_1") (pintype "passive"))
      (node (ref "C37") (pin "1") (pinfunction "1_1") (pintype "passive"))
      (node (ref "C43") (pin "1") (pinfunction "1_1") (pintype "passive"))
      (node (ref "C45") (pin "1") (pinfunction "1_1") (pintype "passive"))
      (node (ref "C6") (pin "1") (pinfunction "1_1") (pintype "passive"))
      (node (ref "CE1") (pin "2") (pinfunction "2_2") (pintype "passive"))
      (node (ref "CE3") (pin "2") (pinfunction "2_2") (pintype "passive"))
      (node (ref "CE4") (pin "2") (pinfunction "2_2") (pintype "passive"))
      (node (ref "CE5") (pin "2") (pinfunction "2_2") (pintype "passive"))
      (node (ref "G2") (pin "1") (pinfunction "1_1") (pintype "passive"))
      (node (ref "G4") (pin "1") (pinfunction "1_1") (pintype "passive"))
      (node (ref "G7") (pin "1") (pinfunction "1_1") (pintype "passive"))
      (node (ref "G8") (pin "1") (pinfunction "1_1") (pintype "passive"))
      (node (ref "GND") (pin "1") (pinfunction "1_1") (pintype "passive"))
      (node (ref "LED_POWER") (pin "2") (pinfunction "K_2") (pintype "passive"))
      (node (ref "P2") (pin "12") (pinfunction "12_12") (pintype "passive"))
      (node (ref "P2") (pin "13") (pinfunction "13_13") (pintype "passive"))
      (node (ref "P2") (pin "14") (pinfunction "14_14") (pintype "passive"))
      (node (ref "P2") (pin "16") (pinfunction "16_16") (pintype "passive"))
      (node (ref "P2") (pin "26") (pinfunction "26_26") (pintype "passive"))
      (node (ref "P2") (pin "27") (pinfunction "27_27") (pintype "passive"))
      (node (ref "P2") (pin "28") (pinfunction "28_28") (pintype "passive"))
      (node (ref "P4") (pin "1") (pinfunction "1_1") (pintype "passive"))
      (node (ref "P8") (pin "1") (pinfunction "1_1") (pintype "passive"))
      (node (ref "R10") (pin "2") (pinfunction "2_2") (pintype "passive"))
      (node (ref "R14") (pin "2") (pinfunction "2_2") (pintype "passive"))
      (node (ref "R32") (pin "2") (pinfunction "2_2") (pintype "passive"))
      (node (ref "R4") (pin "2") (pinfunction "TAP_2") (pintype "passive"))
      (node (ref "R4") (pin "4") (pinfunction "BOT_4") (pintype "passive"))
      (node (ref "R43") (pin "1") (pinfunction "1_1") (pintype "passive"))
      (node (ref "R69") (pin "2") (pinfunction "2_2") (pintype "passive"))
      (node (ref "START") (pin "1") (pinfunction "1_1") (pintype "passive"))
      (node (ref "START") (pin "3") (pinfunction "3_3") (pintype "passive"))
      (node (ref "STOP") (pin "1") (pinfunction "1_1") (pintype "passive"))
      (node (ref "STOP") (pin "3") (pinfunction "3_3") (pintype "passive"))
      (node (ref "U1") (pin "4") (pinfunction "COM_4") (pintype "passive"))
      (node (ref "U2") (pin "4") (pinfunction "COM_4") (pintype "passive"))
      (node (ref "U3") (pin "2") (pinfunction "GND_2") (pintype "passive"))
      (node (ref "U4") (pin "1") (pinfunction "GND_1") (pintype "passive"))
      (node (ref "U5") (pin "4") (pinfunction "COM_4") (pintype "passive"))
    )
    (net (code "65") (name "Net-(AH-G)") (class "Default")
      (node (ref "AH") (pin "1") (pinfunction "G_1") (pintype "passive"))
      (node (ref "C7") (pin "1") (pinfunction "1_1") (pintype "passive"))
      (node (ref "R11") (pin "2") (pinfunction "2_2") (pintype "passive"))
      (node (ref "R21") (pin "2") (pinfunction "2_2") (pintype "passive"))
      (node (ref "R33") (pin "2") (pinfunction "2_2") (pintype "passive"))
    )
    (net (code "66") (name "Net-(AL-G)") (class "Default")
      (node (ref "AL") (pin "1") (pinfunction "G_1") (pintype "passive"))
      (node (ref "C11") (pin "1") (pinfunction "1_1") (pintype "passive"))
      (node (ref "R22") (pin "1") (pinfunction "1_1") (pintype "passive"))
      (node (ref "R31") (pin "2") (pinfunction "2_2") (pintype "passive"))
      (node (ref "R35") (pin "2") (pinfunction "2_2") (pintype "passive"))
    )
    (net (code "67") (name "Net-(BH-G)") (class "Default")
      (node (ref "BH") (pin "1") (pinfunction "G_1") (pintype "passive"))
      (node (ref "C16") (pin "1") (pinfunction "1_1") (pintype "passive"))
      (node (ref "R23") (pin "2") (pinfunction "2_2") (pintype "passive"))
      (node (ref "R36") (pin "2") (pinfunction "2_2") (pintype "passive"))
      (node (ref "R39") (pin "2") (pinfunction "2_2") (pintype "passive"))
    )
    (net (code "68") (name "Net-(BL-G)") (class "Default")
      (node (ref "BL") (pin "1") (pinfunction "G_1") (pintype "passive"))
      (node (ref "C20") (pin "1") (pinfunction "1_1") (pintype "passive"))
      (node (ref "R24") (pin "1") (pinfunction "1_1") (pintype "passive"))
      (node (ref "R37") (pin "2") (pinfunction "2_2") (pintype "passive"))
      (node (ref "R45") (pin "2") (pinfunction "2_2") (pintype "passive"))
    )
    (net (code "69") (name "Net-(CH-G)") (class "Default")
      (node (ref "C24") (pin "1") (pinfunction "1_1") (pintype "passive"))
      (node (ref "CH") (pin "1") (pinfunction "G_1") (pintype "passive"))
      (node (ref "R25") (pin "2") (pinfunction "2_2") (pintype "passive"))
      (node (ref "R38") (pin "2") (pinfunction "2_2") (pintype "passive"))
      (node (ref "R50") (pin "2") (pinfunction "2_2") (pintype "passive"))
    )
    (net (code "70") (name "Net-(CL-G)") (class "Default")
      (node (ref "C34") (pin "1") (pinfunction "1_1") (pintype "passive"))
      (node (ref "CL") (pin "1") (pinfunction "G_1") (pintype "passive"))
      (node (ref "R26") (pin "1") (pinfunction "1_1") (pintype "passive"))
      (node (ref "R40") (pin "2") (pinfunction "2_2") (pintype "passive"))
      (node (ref "R63") (pin "2") (pinfunction "2_2") (pintype "passive"))
    )
    (net (code "71") (name "Net-(D1-A)") (class "Default")
      (node (ref "D1") (pin "1") (pinfunction "A_1") (pintype "passive"))
      (node (ref "R79") (pin "2") (pinfunction "2_2") (pintype "passive"))
    )
    (net (code "72") (name "Net-(D1-K)") (class "Default")
      (node (ref "C28") (pin "1") (pinfunction "1_1") (pintype "passive"))
      (node (ref "D1") (pin "2") (pinfunction "K_2") (pintype "passive"))
      (node (ref "U1") (pin "8") (pinfunction "VB_8") (pintype "passive"))
    )
    (net (code "73") (name "Net-(D2-A)") (class "Default")
      (node (ref "D2") (pin "1") (pinfunction "A_1") (pintype "passive"))
      (node (ref "R78") (pin "2") (pinfunction "2_2") (pintype "passive"))
    )
    (net (code "74") (name "Net-(D2-K)") (class "Default")
      (node (ref "C29") (pin "1") (pinfunction "1_1") (pintype "passive"))
      (node (ref "D2") (pin "2") (pinfunction "K_2") (pintype "passive"))
      (node (ref "U2") (pin "8") (pinfunction "VB_8") (pintype "passive"))
    )
    (net (code "75") (name "Net-(D3-A)") (class "Default")
      (node (ref "D3") (pin "1") (pinfunction "A_1") (pintype "passive"))
      (node (ref "R33") (pin "1") (pinfunction "1_1") (pintype "passive"))
    )
    (net (code "76") (name "Net-(D4-A)") (class "Default")
      (node (ref "D4") (pin "1") (pinfunction "A_1") (pintype "passive"))
      (node (ref "R77") (pin "2") (pinfunction "2_2") (pintype "passive"))
    )
    (net (code "77") (name "Net-(D4-K)") (class "Default")
      (node (ref "C30") (pin "1") (pinfunction "1_1") (pintype "passive"))
      (node (ref "D4") (pin "2") (pinfunction "K_2") (pintype "passive"))
      (node (ref "U5") (pin "8") (pinfunction "VB_8") (pintype "passive"))
    )
    (net (code "78") (name "Net-(D7-K)") (class "Default")
      (node (ref "CE3") (pin "1") (pinfunction "1_1") (pintype "passive"))
      (node (ref "D7") (pin "2") (pinfunction "K_2") (pintype "passive"))
      (node (ref "U4") (pin "5") (pinfunction "DRAIN_5") (pintype "passive"))
    )
    (net (code "79") (name "Net-(D8-A)") (class "Default")
      (node (ref "D8") (pin "1") (pinfunction "A_1") (pintype "passive"))
      (node (ref "R35") (pin "1") (pinfunction "1_1") (pintype "passive"))
    )
    (net (code "80") (name "Net-(D9-A)") (class "Default")
      (node (ref "D9") (pin "1") (pinfunction "A_1") (pintype "passive"))
      (node (ref "R36") (pin "1") (pinfunction "1_1") (pintype "passive"))
    )
    (net (code "81") (name "Net-(D10-A)") (class "Default")
      (node (ref "D10") (pin "1") (pinfunction "A_1") (pintype "passive"))
      (node (ref "R37") (pin "1") (pinfunction "1_1") (pintype "passive"))
    )
    (net (code "82") (name "Net-(D11-A)") (class "Default")
      (node (ref "D11") (pin "1") (pinfunction "A_1") (pintype "passive"))
      (node (ref "R38") (pin "1") (pinfunction "1_1") (pintype "passive"))
    )
    (net (code "83") (name "Net-(D12-A)") (class "Default")
      (node (ref "D12") (pin "1") (pinfunction "A_1") (pintype "passive"))
      (node (ref "R40") (pin "1") (pinfunction "1_1") (pintype "passive"))
    )
    (net (code "84") (name "Net-(LED1-K)") (class "Default")
      (node (ref "LED1") (pin "2") (pinfunction "K_2") (pintype "passive"))
      (node (ref "R10") (pin "1") (pinfunction "1_1") (pintype "passive"))
    )
    (net (code "85") (name "Net-(LED2-K)") (class "Default")
      (node (ref "LED2") (pin "2") (pinfunction "K_2") (pintype "passive"))
      (node (ref "R14") (pin "1") (pinfunction "1_1") (pintype "passive"))
    )
    (net (code "86") (name "Net-(LED3-K)") (class "Default")
      (node (ref "LED3") (pin "2") (pinfunction "K_2") (pintype "passive"))
      (node (ref "R27") (pin "1") (pinfunction "1_1") (pintype "passive"))
    )
    (net (code "87") (name "Net-(LED_POWER-A)") (class "Default")
      (node (ref "LED_POWER") (pin "1") (pinfunction "A_1") (pintype "passive"))
      (node (ref "R65") (pin "2") (pinfunction "2_2") (pintype "passive"))
    )
    (net (code "88") (name "Net-(P4-Pad2)") (class "Default")
      (node (ref "P4") (pin "2") (pinfunction "2_2") (pintype "passive"))
      (node (ref "R12") (pin "1") (pinfunction "1_1") (pintype "passive"))
    )
    (net (code "89") (name "Net-(P4-Pad3)") (class "Default")
      (node (ref "P4") (pin "3") (pinfunction "3_3") (pintype "passive"))
      (node (ref "R9") (pin "2") (pinfunction "2_2") (pintype "passive"))
    )
    (net (code "90") (name "Net-(R1-Pad1)") (class "Default")
      (node (ref "R1") (pin "1") (pinfunction "1_1") (pintype "passive"))
      (node (ref "R55") (pin "2") (pinfunction "2_2") (pintype "passive"))
    )
    (net (code "91") (name "Net-(R2-Pad1)") (class "Default")
      (node (ref "R2") (pin "1") (pinfunction "1_1") (pintype "passive"))
      (node (ref "R59") (pin "2") (pinfunction "2_2") (pintype "passive"))
    )
    (net (code "92") (name "Net-(R3-Pad1)") (class "Default")
      (node (ref "R3") (pin "1") (pinfunction "1_1") (pintype "passive"))
      (node (ref "R61") (pin "2") (pinfunction "2_2") (pintype "passive"))
    )
    (net (code "93") (name "Net-(R74-Pad2)") (class "Default")
      (node (ref "R74") (pin "2") (pinfunction "2_2") (pintype "passive"))
      (node (ref "R75") (pin "1") (pinfunction "1_1") (pintype "passive"))
    )
    (net (code "94") (name "Net-(U3-Vin)") (class "Default")
      (node (ref "R18") (pin "2") (pinfunction "2_2") (pintype "passive"))
      (node (ref "U3") (pin "3") (pinfunction "Vin_3") (pintype "passive"))
    )
    (net (code "95") (name "Net-(U4-CS)") (class "Default")
      (node (ref "R34") (pin "1") (pinfunction "1_1") (pintype "passive"))
      (node (ref "U4") (pin "7") (pinfunction "CS_7") (pintype "passive"))
    )
    (net (code "96") (name "Net-(U4-IC_GND)") (class "Default")
      (node (ref "C1") (pin "2") (pinfunction "2_2") (pintype "passive"))
      (node (ref "L1") (pin "2") (pinfunction "2_2") (pintype "passive"))
      (node (ref "R34") (pin "2") (pinfunction "2_2") (pintype "passive"))
      (node (ref "U4") (pin "8") (pinfunction "IC_GND_8") (pintype "passive"))
    )
    (net (code "97") (name "Net-(U4-VCC)") (class "Default")
      (node (ref "C1") (pin "1") (pinfunction "1_1") (pintype "passive"))
      (node (ref "U4") (pin "4") (pinfunction "VCC_4") (pintype "passive"))
    )
    (net (code "98") (name "PGND") (class "Default")
      (node (ref "C25") (pin "1") (pinfunction "1_1") (pintype "passive"))
      (node (ref "C26") (pin "1") (pinfunction "1_1") (pintype "passive"))
      (node (ref "C27") (pin "1") (pinfunction "1_1") (pintype "passive"))
      (node (ref "CE2") (pin "2") (pinfunction "2_2") (pintype "passive"))
      (node (ref "G1") (pin "1") (pinfunction "1_1") (pintype "passive"))
      (node (ref "P1") (pin "1") (pinfunction "1_1") (pintype "passive"))
      (node (ref "P1") (pin "2") (pinfunction "2_2") (pintype "passive"))
      (node (ref "P2") (pin "1") (pinfunction "1_1") (pintype "passive"))
      (node (ref "P2") (pin "2") (pinfunction "2_2") (pintype "passive"))
      (node (ref "R15") (pin "2") (pinfunction "2_2") (pintype "passive"))
      (node (ref "R16") (pin "1") (pinfunction "1_1") (pintype "passive"))
      (node (ref "R17") (pin "2") (pinfunction "2_2") (pintype "passive"))
      (node (ref "R28") (pin "1") (pinfunction "1_1") (pintype "passive"))
      (node (ref "R29") (pin "1") (pinfunction "1_1") (pintype "passive"))
      (node (ref "R30") (pin "1") (pinfunction "1_1") (pintype "passive"))
      (node (ref "R49") (pin "2") (pinfunction "2_2") (pintype "passive"))
      (node (ref "R69") (pin "1") (pinfunction "1_1") (pintype "passive"))
    )
    (net (code "99") (name "unconnected-(U4-NC-Pad3)") (class "Default")
      (node (ref "U4") (pin "3") (pinfunction "NC_3") (pintype "passive+no_connect"))
    )
    (net (code "100") (name "unconnected-(U4-NC-Pad6)") (class "Default")
      (node (ref "U4") (pin "6") (pinfunction "NC_6") (pintype "passive+no_connect"))
    )
  )
)
